# PWR_Buck_6V_8A.net
KiCad netlist of a schematic drawn in Altium Designer
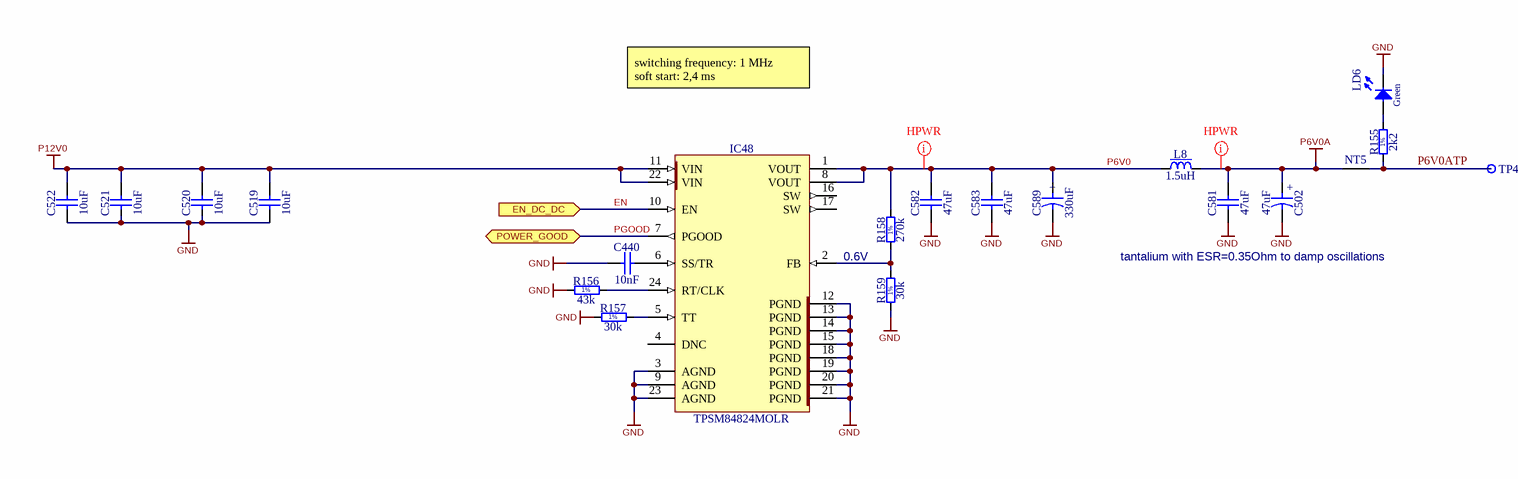
[diagram p0: PWR_Buck_6V_8A.SchDoc]

(export (version "E")
  (design (tool "Eeschema 10.0.6"))
  (components
    (comp (ref "C440")
      (value "10nF")
      (footprint "CAPC1005X55N")
      (description "Non-polarised capacitor")
      (fields
        (field (name "MANUFACTURER PART NUMBER") "CC0402_10NF_16V_10%_X7R")
        (field (name "MANUFACTURER") "GENERIC")
        (field (name "AUTHOR") "CERN DEM JLC")
      )
      (libsource (lib "Capacitors") (part "Capacitor - non polarized"))
    )
    (comp (ref "C502")
      (value "47uF")
      (footprint "CAPMP6032X280N")
      (description "Polarised capacitor")
      (fields
        (field (name "MANUFACTURER PART NUMBER") "CTE6032-28_47UF_16V_10%_LESR0350")
        (field (name "MANUFACTURER") "GENERIC")
        (field (name "AUTHOR") "CERN DEM JLC")
      )
      (libsource (lib "") (part "Capacitor - polarized_1"))
    )
    (comp (ref "C519")
      (value "10uF")
      (footprint "CAPC2012X95N")
      (description "Non-polarised capacitor")
      (fields
        (field (name "MANUFACTURER PART NUMBER") "CC0805_10UF_25V_10%_X5R")
        (field (name "MANUFACTURER") "GENERIC")
        (field (name "AUTHOR") "CERN DEM JLC")
      )
      (libsource (lib "Capacitors") (part "Capacitor - non polarized"))
    )
    (comp (ref "C520")
      (value "10uF")
      (footprint "CAPC2012X95N")
      (description "Non-polarised capacitor")
      (fields
        (field (name "MANUFACTURER PART NUMBER") "CC0805_10UF_25V_10%_X5R")
        (field (name "MANUFACTURER") "GENERIC")
        (field (name "AUTHOR") "CERN DEM JLC")
      )
      (libsource (lib "Capacitors") (part "Capacitor - non polarized"))
    )
    (comp (ref "C521")
      (value "10uF")
      (footprint "CAPC2012X95N")
      (description "Non-polarised capacitor")
      (fields
        (field (name "MANUFACTURER PART NUMBER") "CC0805_10UF_25V_10%_X5R")
        (field (name "MANUFACTURER") "GENERIC")
        (field (name "AUTHOR") "CERN DEM JLC")
      )
      (libsource (lib "Capacitors") (part "Capacitor - non polarized"))
    )
    (comp (ref "C522")
      (value "10uF")
      (footprint "CAPC2012X95N")
      (description "Non-polarised capacitor")
      (fields
        (field (name "MANUFACTURER PART NUMBER") "CC0805_10UF_25V_10%_X5R")
        (field (name "MANUFACTURER") "GENERIC")
        (field (name "AUTHOR") "CERN DEM JLC")
      )
      (libsource (lib "Capacitors") (part "Capacitor - non polarized"))
    )
    (comp (ref "C581")
      (value "47uF")
      (footprint "CAPC3225X270N")
      (description "Non-polarised capacitor")
      (fields
        (field (name "MANUFACTURER PART NUMBER") "CC1210_47UF_10V_10%_X7R")
        (field (name "MANUFACTURER") "GENERIC")
        (field (name "AUTHOR") "CERN DEM BC")
      )
      (libsource (lib "Capacitors") (part "Capacitor - non polarized"))
    )
    (comp (ref "C582")
      (value "47uF")
      (footprint "CAPC3225X270N")
      (description "Non-polarised capacitor")
      (fields
        (field (name "MANUFACTURER PART NUMBER") "CC1210_47UF_10V_10%_X7R")
        (field (name "MANUFACTURER") "GENERIC")
        (field (name "AUTHOR") "CERN DEM BC")
      )
      (libsource (lib "Capacitors") (part "Capacitor - non polarized"))
    )
    (comp (ref "C583")
      (value "47uF")
      (footprint "CAPC3225X270N")
      (description "Non-polarised capacitor")
      (fields
        (field (name "MANUFACTURER PART NUMBER") "CC1210_47UF_10V_10%_X7R")
        (field (name "MANUFACTURER") "GENERIC")
        (field (name "AUTHOR") "CERN DEM BC")
      )
      (libsource (lib "Capacitors") (part "Capacitor - non polarized"))
    )
    (comp (ref "C589")
      (value "330uF")
      (footprint "CAPMP7343X310N")
      (description "Polarised capacitor")
      (fields
        (field (name "MANUFACTURER PART NUMBER") "T520D337M006ATE015")
        (field (name "MANUFACTURER") "KEMET")
        (field (name "AUTHOR") "CERN DEM JLC")
      )
      (libsource (lib "Capacitors") (part "Capacitor - polarized"))
    )
    (comp (ref "IC48")
      (value "TPSM84824MOLR")
      (footprint "TEXAS_QFM (MOL)")
      (description "4.5V to 17V Input, 0.6V to 10V Output, 8A Power Module")
      (fields (field (name "MANUFACTURER") "TEXAS INSTRUMENTS") (field (name "AUTHOR") "CERN DEM JLC"))
      (libsource (lib "ICs And Semiconductors") (part "TPSM84824"))
    )
    (comp (ref "L8")
      (value "1.5uH")
      (footprint "IND_TDK_SPM6530")
      (description "Inductor With Core")
      (fields
        (field (name "MANUFACTURER PART NUMBER") "SPM6530T-1R5M100")
        (field (name "MANUFACTURER") "TDK")
        (field (name "AUTHOR") "CERN DEM MR")
      )
      (libsource (lib "Inductors & Transformers") (part "Inductor With Magnetic core"))
    )
    (comp (ref "LD6")
      (value "Green")
      (footprint "LED_KINGBRIGHT_KPH-1608CGCK")
      (description "LED Green 1C 2A")
      (fields
        (field (name "MANUFACTURER PART NUMBER") "KPH-1608CGCK")
        (field (name "MANUFACTURER") "KINGBRIGHT")
        (field (name "AUTHOR") "CERN DEM JLC")
      )
      (libsource (lib "ICs And Semiconductors") (part "LED Green 1C 2A"))
    )
    (comp (ref "NT5")
      (value "Net Tie")
      (footprint "Net Tie")
      (fields (field (name "AUTHOR") "CERN DEM JLC"))
      (libsource (lib "Eletro-mechanical") (part "Net Tie"))
    )
    (comp (ref "R155")
      (value "2k2")
      (footprint "RESC1005X40N")
      (description "Resistor - 1%")
      (fields
        (field (name "MANUFACTURER PART NUMBER") "R0402_2K2_1%_0.0625W_100PPM")
        (field (name "MANUFACTURER") "GENERIC")
        (field (name "AUTHOR") "CERN DEM JLC")
      )
      (libsource (lib "Resistors") (part "Resistor - 1%"))
    )
    (comp (ref "R156")
      (value "43k")
      (footprint "RESC1005X40N")
      (description "Resistor - 1%")
      (fields
        (field (name "MANUFACTURER PART NUMBER") "R0402_43K_1%_0.0625W_100PPM")
        (field (name "MANUFACTURER") "GENERIC")
        (field (name "AUTHOR") "CERN DEM JLC")
      )
      (libsource (lib "Resistors") (part "Resistor - 1%"))
    )
    (comp (ref "R157")
      (value "30k")
      (footprint "RESC1005X40N")
      (description "Resistor - 1%")
      (fields
        (field (name "MANUFACTURER PART NUMBER") "R0402_30K_1%_0.0625W_100PPM")
        (field (name "MANUFACTURER") "GENERIC")
        (field (name "AUTHOR") "CERN DEM JLC")
      )
      (libsource (lib "Resistors") (part "Resistor - 1%"))
    )
    (comp (ref "R158")
      (value "270k")
      (footprint "RESC1005X40N")
      (description "Resistor - 1%")
      (fields
        (field (name "MANUFACTURER PART NUMBER") "R0402_270K_1%_0.0625W_100PPM")
        (field (name "MANUFACTURER") "GENERIC")
        (field (name "AUTHOR") "CERN DEM JLC")
      )
      (libsource (lib "Resistors") (part "Resistor - 1%"))
    )
    (comp (ref "R159")
      (value "30k")
      (footprint "RESC1005X40N")
      (description "Resistor - 1%")
      (fields
        (field (name "MANUFACTURER PART NUMBER") "R0402_30K_1%_0.0625W_100PPM")
        (field (name "MANUFACTURER") "GENERIC")
        (field (name "AUTHOR") "CERN DEM JLC")
      )
      (libsource (lib "Resistors") (part "Resistor - 1%"))
    )
    (comp (ref "TP48")
      (value "Test Point")
      (footprint "TPS127")
      (fields (field (name "PART NUMBER") "SMD_PAD_1.27X1.27MM") (field (name "AUTHOR") "CERN DEM JLC"))
      (libsource (lib "Eletro-mechanical") (part "Test Point"))
    )
  )
  (nets
    (net (code "1") (name "/EN") (class "Default")
      (node (ref "IC48") (pin "10") (pinfunction "EN_10") (pintype "input"))
    )
    (net (code "2") (name "/P6V0") (class "Default")
      (node (ref "C582") (pin "2") (pinfunction "2_2") (pintype "passive"))
      (node (ref "C583") (pin "2") (pinfunction "2_2") (pintype "passive"))
      (node (ref "C589") (pin "1") (pinfunction "1_1") (pintype "passive"))
      (node (ref "IC48") (pin "1") (pinfunction "VOUT_1") (pintype "power_in"))
      (node (ref "IC48") (pin "8") (pinfunction "VOUT_8") (pintype "power_in"))
      (node (ref "L8") (pin "1") (pinfunction "1_1") (pintype "passive"))
      (node (ref "R158") (pin "2") (pinfunction "2_2") (pintype "passive"))
    )
    (net (code "3") (name "/P6V0ATP") (class "Default")
      (node (ref "NT5") (pin "2") (pinfunction "2_2") (pintype "bidirectional"))
      (node (ref "R155") (pin "1") (pinfunction "1_1") (pintype "passive"))
      (node (ref "TP48") (pin "1") (pinfunction "1_1") (pintype "bidirectional"))
    )
    (net (code "4") (name "/PGOOD") (class "Default")
      (node (ref "IC48") (pin "7") (pinfunction "PGOOD_7") (pintype "output"))
    )
    (net (code "5") (name "GND") (class "Default")
      (node (ref "C440") (pin "1") (pinfunction "1_1") (pintype "passive"))
      (node (ref "C502") (pin "2") (pinfunction "2_2") (pintype "passive"))
      (node (ref "C519") (pin "1") (pinfunction "1_1") (pintype "passive"))
      (node (ref "C520") (pin "1") (pinfunction "1_1") (pintype "passive"))
      (node (ref "C521") (pin "1") (pinfunction "1_1") (pintype "passive"))
      (node (ref "C522") (pin "1") (pinfunction "1_1") (pintype "passive"))
      (node (ref "C581") (pin "1") (pinfunction "1_1") (pintype "passive"))
      (node (ref "C582") (pin "1") (pinfunction "1_1") (pintype "passive"))
      (node (ref "C583") (pin "1") (pinfunction "1_1") (pintype "passive"))
      (node (ref "C589") (pin "2") (pinfunction "2_2") (pintype "passive"))
      (node (ref "IC48") (pin "12") (pinfunction "PGND_12") (pintype "power_in"))
      (node (ref "IC48") (pin "13") (pinfunction "PGND_13") (pintype "power_in"))
      (node (ref "IC48") (pin "14") (pinfunction "PGND_14") (pintype "power_in"))
      (node (ref "IC48") (pin "15") (pinfunction "PGND_15") (pintype "power_in"))
      (node (ref "IC48") (pin "18") (pinfunction "PGND_18") (pintype "power_in"))
      (node (ref "IC48") (pin "19") (pinfunction "PGND_19") (pintype "power_in"))
      (node (ref "IC48") (pin "20") (pinfunction "PGND_20") (pintype "power_in"))
      (node (ref "IC48") (pin "21") (pinfunction "PGND_21") (pintype "power_in"))
      (node (ref "IC48") (pin "23") (pinfunction "AGND_23") (pintype "power_in"))
      (node (ref "IC48") (pin "3") (pinfunction "AGND_3") (pintype "power_in"))
      (node (ref "IC48") (pin "9") (pinfunction "AGND_9") (pintype "power_in"))
      (node (ref "LD6") (pin "1") (pinfunction "C_1") (pintype "passive"))
      (node (ref "R156") (pin "1") (pinfunction "1_1") (pintype "passive"))
      (node (ref "R157") (pin "1") (pinfunction "1_1") (pintype "passive"))
      (node (ref "R159") (pin "1") (pinfunction "1_1") (pintype "passive"))
    )
    (net (code "6") (name "Net-(IC48-FB)") (class "Default")
      (node (ref "IC48") (pin "2") (pinfunction "FB_2") (pintype "input"))
      (node (ref "R158") (pin "1") (pinfunction "1_1") (pintype "passive"))
      (node (ref "R159") (pin "2") (pinfunction "2_2") (pintype "passive"))
    )
    (net (code "7") (name "Net-(IC48-RT{slash}CLK)") (class "Default")
      (node (ref "IC48") (pin "24") (pinfunction "RT/CLK_24") (pintype "input"))
      (node (ref "R156") (pin "2") (pinfunction "2_2") (pintype "passive"))
    )
    (net (code "8") (name "Net-(IC48-SS{slash}TR)") (class "Default")
      (node (ref "C440") (pin "2") (pinfunction "2_2") (pintype "passive"))
      (node (ref "IC48") (pin "6") (pinfunction "SS/TR_6") (pintype "input"))
    )
    (net (code "9") (name "Net-(IC48-TT)") (class "Default")
      (node (ref "IC48") (pin "5") (pinfunction "TT_5") (pintype "input"))
      (node (ref "R157") (pin "2") (pinfunction "2_2") (pintype "passive"))
    )
    (net (code "10") (name "Net-(LD6-A)") (class "Default")
      (node (ref "LD6") (pin "2") (pinfunction "A_2") (pintype "passive"))
      (node (ref "R155") (pin "2") (pinfunction "2_2") (pintype "passive"))
    )
    (net (code "11") (name "P6V0A") (class "Default")
      (node (ref "C502") (pin "1") (pinfunction "1_1") (pintype "passive"))
      (node (ref "C581") (pin "2") (pinfunction "2_2") (pintype "passive"))
      (node (ref "L8") (pin "2") (pinfunction "2_2") (pintype "passive"))
      (node (ref "NT5") (pin "1") (pinfunction "1_1") (pintype "bidirectional"))
    )
    (net (code "12") (name "P12V0") (class "Default")
      (node (ref "C519") (pin "2") (pinfunction "2_2") (pintype "passive"))
      (node (ref "C520") (pin "2") (pinfunction "2_2") (pintype "passive"))
      (node (ref "C521") (pin "2") (pinfunction "2_2") (pintype "passive"))
      (node (ref "C522") (pin "2") (pinfunction "2_2") (pintype "passive"))
      (node (ref "IC48") (pin "11") (pinfunction "VIN_11") (pintype "input"))
      (node (ref "IC48") (pin "22") (pinfunction "VIN_22") (pintype "input"))
    )
    (net (code "13") (name "unconnected-(IC48-DNC-Pad4)") (class "Default")
      (node (ref "IC48") (pin "4") (pinfunction "DNC_4") (pintype "passive"))
    )
    (net (code "14") (name "unconnected-(IC48-SW-Pad16)") (class "Default")
      (node (ref "IC48") (pin "16") (pinfunction "SW_16") (pintype "output"))
    )
    (net (code "15") (name "unconnected-(IC48-SW-Pad17)") (class "Default")
      (node (ref "IC48") (pin "17") (pinfunction "SW_17") (pintype "output"))
    )
  )
)
